# POWER_IO.net
KiCad netlist of a schematic drawn in Altium Designer
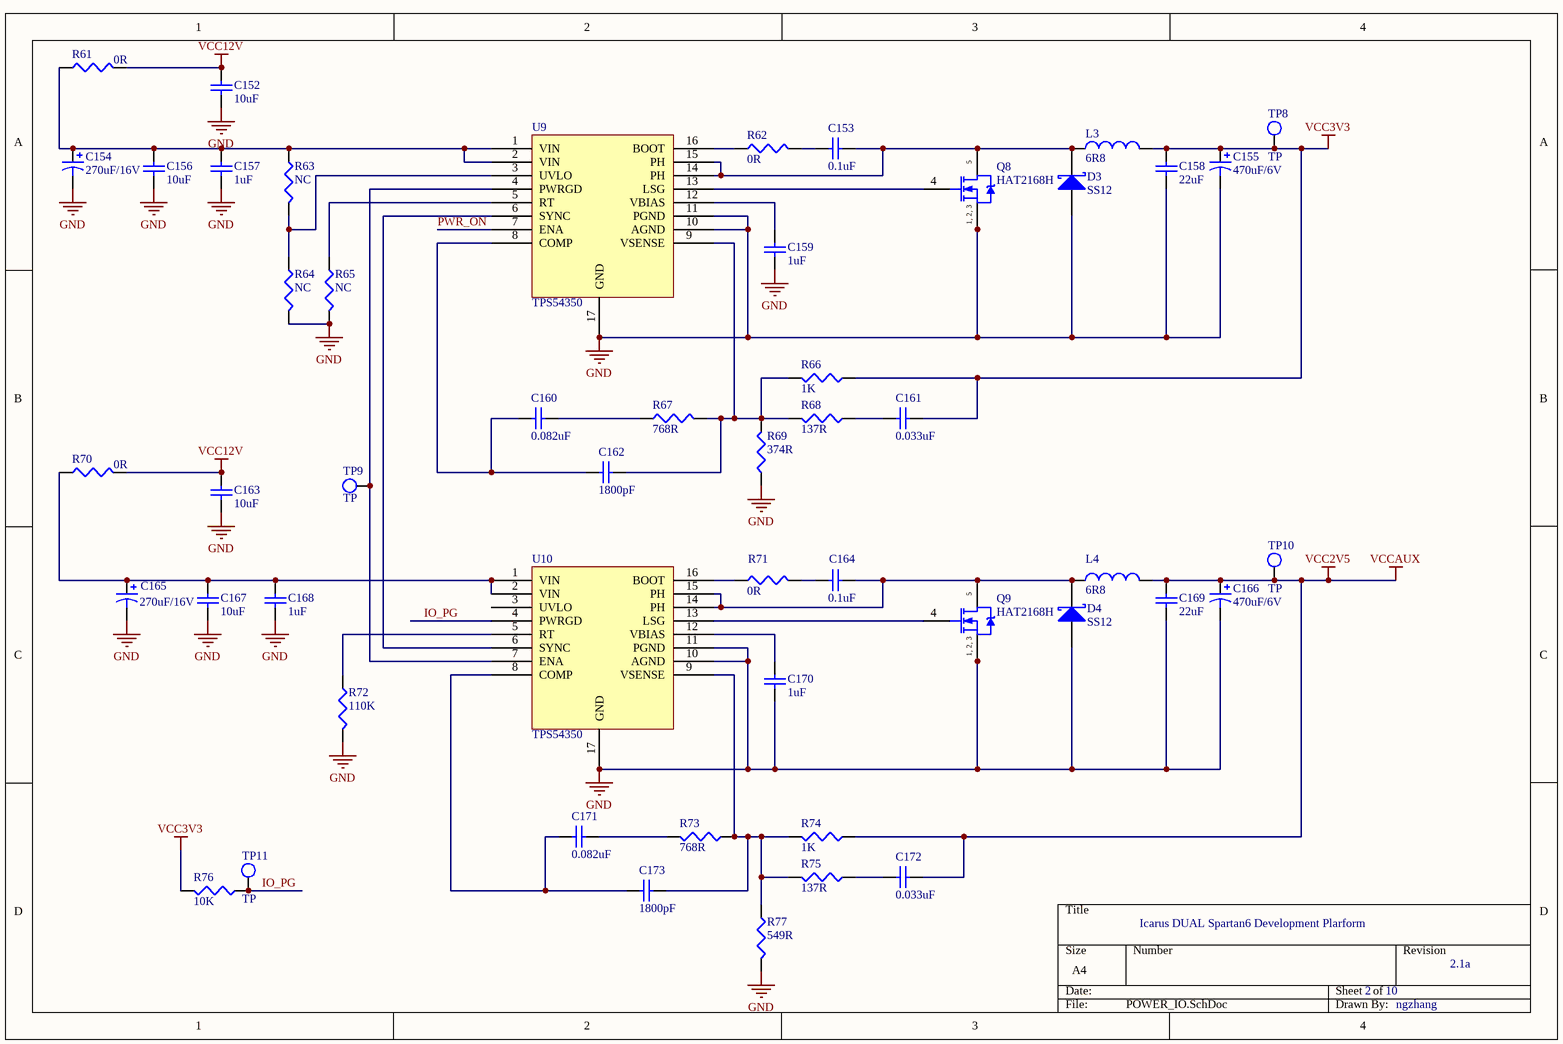
[diagram p0: POWER_IO.SchDoc]

(export (version "E")
  (design (tool "Eeschema 10.0.6"))
  (components
    (comp (ref "C152")
      (value "10uF")
      (footprint "C1206")
      (description "Capacitor (Semiconductor SIM Model)")
      (fields (field (name "PUBLISHER") "Altium Limited"))
      (libsource (lib "Miscellaneous Devices") (part "Cap Semi"))
    )
    (comp (ref "C153")
      (value "0.1uF")
      (footprint "1608[0603]")
      (description "Capacitor (Semiconductor SIM Model)")
      (fields (field (name "PUBLISHER") "Altium Limited"))
      (libsource (lib "Miscellaneous Devices") (part "Cap Semi"))
    )
    (comp (ref "C154")
      (value "270uF/16V")
      (footprint "CAP8X8")
      (description "Polarized Capacitor (Surface Mount)")
      (fields (field (name "PUBLISHER") "Altium Limited"))
      (libsource (lib "Miscellaneous Devices") (part "Cap Pol3"))
    )
    (comp (ref "C155")
      (value "470uF/6V")
      (footprint "CAP8X8")
      (description "Polarized Capacitor (Surface Mount)")
      (fields (field (name "PUBLISHER") "Altium Limited"))
      (libsource (lib "Miscellaneous Devices") (part "Cap Pol3"))
    )
    (comp (ref "C156")
      (value "10uF")
      (footprint "C1206")
      (description "Capacitor (Semiconductor SIM Model)")
      (fields (field (name "PUBLISHER") "Altium Limited"))
      (libsource (lib "Miscellaneous Devices") (part "Cap Semi"))
    )
    (comp (ref "C157")
      (value "1uF")
      (footprint "1608[0603]")
      (description "Capacitor (Semiconductor SIM Model)")
      (fields (field (name "PUBLISHER") "Altium Limited"))
      (libsource (lib "Miscellaneous Devices") (part "Cap Semi"))
    )
    (comp (ref "C158")
      (value "22uF")
      (footprint "C1206")
      (description "Capacitor (Semiconductor SIM Model)")
      (fields (field (name "PUBLISHER") "Altium Limited"))
      (libsource (lib "Miscellaneous Devices") (part "Cap Semi"))
    )
    (comp (ref "C159")
      (value "1uF")
      (footprint "1608[0603]")
      (description "Capacitor (Semiconductor SIM Model)")
      (fields (field (name "PUBLISHER") "Altium Limited"))
      (libsource (lib "Miscellaneous Devices") (part "Cap Semi"))
    )
    (comp (ref "C160")
      (value "0.082uF")
      (footprint "1608[0603]")
      (description "Capacitor (Semiconductor SIM Model)")
      (fields (field (name "PUBLISHER") "Altium Limited"))
      (libsource (lib "Miscellaneous Devices") (part "Cap Semi"))
    )
    (comp (ref "C161")
      (value "0.033uF")
      (footprint "1608[0603]")
      (description "Capacitor (Semiconductor SIM Model)")
      (fields (field (name "PUBLISHER") "Altium Limited"))
      (libsource (lib "Miscellaneous Devices") (part "Cap Semi"))
    )
    (comp (ref "C162")
      (value "1800pF")
      (footprint "1608[0603]")
      (description "Capacitor (Semiconductor SIM Model)")
      (fields (field (name "PUBLISHER") "Altium Limited"))
      (libsource (lib "Miscellaneous Devices") (part "Cap Semi"))
    )
    (comp (ref "C163")
      (value "10uF")
      (footprint "C1206")
      (description "Capacitor (Semiconductor SIM Model)")
      (fields (field (name "PUBLISHER") "Altium Limited"))
      (libsource (lib "Miscellaneous Devices") (part "Cap Semi"))
    )
    (comp (ref "C164")
      (value "0.1uF")
      (footprint "1608[0603]")
      (description "Capacitor (Semiconductor SIM Model)")
      (fields (field (name "PUBLISHER") "Altium Limited"))
      (libsource (lib "Miscellaneous Devices") (part "Cap Semi"))
    )
    (comp (ref "C165")
      (value "270uF/16V")
      (footprint "CAP8X8")
      (description "Polarized Capacitor (Surface Mount)")
      (fields (field (name "PUBLISHER") "Altium Limited"))
      (libsource (lib "Miscellaneous Devices") (part "Cap Pol3"))
    )
    (comp (ref "C166")
      (value "470uF/6V")
      (footprint "CAP8X8")
      (description "Polarized Capacitor (Surface Mount)")
      (fields (field (name "PUBLISHER") "Altium Limited"))
      (libsource (lib "Miscellaneous Devices") (part "Cap Pol3"))
    )
    (comp (ref "C167")
      (value "10uF")
      (footprint "C1206")
      (description "Capacitor (Semiconductor SIM Model)")
      (fields (field (name "PUBLISHER") "Altium Limited"))
      (libsource (lib "Miscellaneous Devices") (part "Cap Semi"))
    )
    (comp (ref "C168")
      (value "1uF")
      (footprint "1608[0603]")
      (description "Capacitor (Semiconductor SIM Model)")
      (fields (field (name "PUBLISHER") "Altium Limited"))
      (libsource (lib "Miscellaneous Devices") (part "Cap Semi"))
    )
    (comp (ref "C169")
      (value "22uF")
      (footprint "C1206")
      (description "Capacitor (Semiconductor SIM Model)")
      (fields (field (name "PUBLISHER") "Altium Limited"))
      (libsource (lib "Miscellaneous Devices") (part "Cap Semi"))
    )
    (comp (ref "C170")
      (value "1uF")
      (footprint "1608[0603]")
      (description "Capacitor (Semiconductor SIM Model)")
      (fields (field (name "PUBLISHER") "Altium Limited"))
      (libsource (lib "Miscellaneous Devices") (part "Cap Semi"))
    )
    (comp (ref "C171")
      (value "0.082uF")
      (footprint "1608[0603]")
      (description "Capacitor (Semiconductor SIM Model)")
      (fields (field (name "PUBLISHER") "Altium Limited"))
      (libsource (lib "Miscellaneous Devices") (part "Cap Semi"))
    )
    (comp (ref "C172")
      (value "0.033uF")
      (footprint "1608[0603]")
      (description "Capacitor (Semiconductor SIM Model)")
      (fields (field (name "PUBLISHER") "Altium Limited"))
      (libsource (lib "Miscellaneous Devices") (part "Cap Semi"))
    )
    (comp (ref "C173")
      (value "1800pF")
      (footprint "1608[0603]")
      (description "Capacitor (Semiconductor SIM Model)")
      (fields (field (name "PUBLISHER") "Altium Limited"))
      (libsource (lib "Miscellaneous Devices") (part "Cap Semi"))
    )
    (comp (ref "D3")
      (value "SS12")
      (footprint "SMA")
      (description "Schottky Rectifier")
      (fields (field (name "PUBLISHER") "Altium Limited"))
      (libsource (lib "IR Rectifier - Schottky") (part "10MQ060N"))
    )
    (comp (ref "D4")
      (value "SS12")
      (footprint "SMA")
      (description "Schottky Rectifier")
      (fields (field (name "PUBLISHER") "Altium Limited"))
      (libsource (lib "IR Rectifier - Schottky") (part "10MQ060N"))
    )
    (comp (ref "L3")
      (value "6R8")
      (footprint "IHLP4040")
      (description "Inductor")
      (fields (field (name "Comment") "IHLP4040DZ11") (field (name "PUBLISHER") "Altium Limited"))
      (libsource (lib "Miscellaneous Devices") (part "Inductor"))
    )
    (comp (ref "L4")
      (value "6R8")
      (footprint "IHLP4040")
      (description "Inductor")
      (fields (field (name "Comment") "IHLP4040DZ11") (field (name "PUBLISHER") "Altium Limited"))
      (libsource (lib "Miscellaneous Devices") (part "Inductor"))
    )
    (comp (ref "Q8") (value "HAT2168H") (footprint "LFPAK") (libsource (lib "S6") (part "HAT216X")))
    (comp (ref "Q9") (value "HAT2168H") (footprint "LFPAK") (libsource (lib "S6") (part "HAT216X")))
    (comp (ref "R61")
      (value "0R")
      (footprint "C1206")
      (description "Resistor")
      (fields (field (name "PUBLISHER") "Altium Limited"))
      (libsource (lib "Miscellaneous Devices") (part "Res3"))
    )
    (comp (ref "R62")
      (value "0R")
      (footprint "J1-0603")
      (description "Resistor")
      (fields (field (name "PUBLISHER") "Altium Limited"))
      (libsource (lib "Miscellaneous Devices") (part "Res3"))
    )
    (comp (ref "R63")
      (value "NC")
      (footprint "J1-0603")
      (description "Resistor")
      (fields (field (name "PUBLISHER") "Altium Limited"))
      (libsource (lib "Miscellaneous Devices") (part "Res3"))
    )
    (comp (ref "R64")
      (value "NC")
      (footprint "J1-0603")
      (description "Resistor")
      (fields (field (name "PUBLISHER") "Altium Limited"))
      (libsource (lib "Miscellaneous Devices") (part "Res3"))
    )
    (comp (ref "R65")
      (value "NC")
      (footprint "J1-0603")
      (description "Resistor")
      (fields (field (name "PUBLISHER") "Altium Limited"))
      (libsource (lib "Miscellaneous Devices") (part "Res3"))
    )
    (comp (ref "R66")
      (value "1K")
      (footprint "J1-0603")
      (description "Resistor")
      (fields (field (name "PUBLISHER") "Altium Limited"))
      (libsource (lib "Miscellaneous Devices") (part "Res3"))
    )
    (comp (ref "R67")
      (value "768R")
      (footprint "J1-0603")
      (description "Resistor")
      (fields (field (name "PUBLISHER") "Altium Limited"))
      (libsource (lib "Miscellaneous Devices") (part "Res3"))
    )
    (comp (ref "R68")
      (value "137R")
      (footprint "J1-0603")
      (description "Resistor")
      (fields (field (name "PUBLISHER") "Altium Limited"))
      (libsource (lib "Miscellaneous Devices") (part "Res3"))
    )
    (comp (ref "R69")
      (value "374R")
      (footprint "J1-0603")
      (description "Resistor")
      (fields (field (name "PUBLISHER") "Altium Limited"))
      (libsource (lib "Miscellaneous Devices") (part "Res3"))
    )
    (comp (ref "R70")
      (value "0R")
      (footprint "C1206")
      (description "Resistor")
      (fields (field (name "PUBLISHER") "Altium Limited"))
      (libsource (lib "Miscellaneous Devices") (part "Res3"))
    )
    (comp (ref "R71")
      (value "0R")
      (footprint "J1-0603")
      (description "Resistor")
      (fields (field (name "PUBLISHER") "Altium Limited"))
      (libsource (lib "Miscellaneous Devices") (part "Res3"))
    )
    (comp (ref "R72")
      (value "110K")
      (footprint "J1-0603")
      (description "Resistor")
      (fields (field (name "PUBLISHER") "Altium Limited"))
      (libsource (lib "Miscellaneous Devices") (part "Res3"))
    )
    (comp (ref "R73")
      (value "768R")
      (footprint "J1-0603")
      (description "Resistor")
      (fields (field (name "PUBLISHER") "Altium Limited"))
      (libsource (lib "Miscellaneous Devices") (part "Res3"))
    )
    (comp (ref "R74")
      (value "1K")
      (footprint "J1-0603")
      (description "Resistor")
      (fields (field (name "PUBLISHER") "Altium Limited"))
      (libsource (lib "Miscellaneous Devices") (part "Res3"))
    )
    (comp (ref "R75")
      (value "137R")
      (footprint "J1-0603")
      (description "Resistor")
      (fields (field (name "PUBLISHER") "Altium Limited"))
      (libsource (lib "Miscellaneous Devices") (part "Res3"))
    )
    (comp (ref "R76")
      (value "10K")
      (footprint "J1-0603")
      (description "Resistor")
      (fields (field (name "PUBLISHER") "Altium Limited"))
      (libsource (lib "Miscellaneous Devices") (part "Res3"))
    )
    (comp (ref "R77")
      (value "549R")
      (footprint "J1-0603")
      (description "Resistor")
      (fields (field (name "PUBLISHER") "Altium Limited"))
      (libsource (lib "Miscellaneous Devices") (part "Res3"))
    )
    (comp (ref "TP8") (value "TP") (footprint "TP") (libsource (lib "S6") (part "TP")))
    (comp (ref "TP9") (value "TP") (footprint "TP") (libsource (lib "S6") (part "TP")))
    (comp (ref "TP10") (value "TP") (footprint "TP") (libsource (lib "S6") (part "TP")))
    (comp (ref "TP11") (value "TP") (footprint "TP") (libsource (lib "S6") (part "TP")))
    (comp (ref "U9") (value "TPS54350") (footprint "TSSOP16_PP") (libsource (lib "S6") (part "TPS54350")))
    (comp (ref "U10") (value "TPS54350") (footprint "TSSOP16_PP") (libsource (lib "S6") (part "TPS54350")))
  )
  (nets
    (net (code "1") (name "/IO_PG") (class "Default")
      (node (ref "R76") (pin "1") (pinfunction "1_1") (pintype "passive"))
      (node (ref "TP11") (pin "1") (pinfunction "TP_1") (pintype "passive"))
      (node (ref "U10") (pin "4") (pinfunction "PWRGD_4") (pintype "passive"))
    )
    (net (code "2") (name "/PWR_ON") (class "Default")
      (node (ref "U9") (pin "7") (pinfunction "ENA_7") (pintype "passive"))
    )
    (net (code "3") (name "GND") (class "Default")
      (node (ref "C152") (pin "1") (pinfunction "1_1") (pintype "passive"))
      (node (ref "C154") (pin "2") (pinfunction "2_2") (pintype "passive"))
      (node (ref "C155") (pin "2") (pinfunction "2_2") (pintype "passive"))
      (node (ref "C156") (pin "1") (pinfunction "1_1") (pintype "passive"))
      (node (ref "C157") (pin "1") (pinfunction "1_1") (pintype "passive"))
      (node (ref "C158") (pin "1") (pinfunction "1_1") (pintype "passive"))
      (node (ref "C159") (pin "1") (pinfunction "1_1") (pintype "passive"))
      (node (ref "C163") (pin "1") (pinfunction "1_1") (pintype "passive"))
      (node (ref "C165") (pin "2") (pinfunction "2_2") (pintype "passive"))
      (node (ref "C166") (pin "2") (pinfunction "2_2") (pintype "passive"))
      (node (ref "C167") (pin "1") (pinfunction "1_1") (pintype "passive"))
      (node (ref "C168") (pin "1") (pinfunction "1_1") (pintype "passive"))
      (node (ref "C169") (pin "1") (pinfunction "1_1") (pintype "passive"))
      (node (ref "C170") (pin "2") (pinfunction "2_2") (pintype "passive"))
      (node (ref "D3") (pin "1") (pinfunction "A_1") (pintype "passive"))
      (node (ref "D4") (pin "1") (pinfunction "A_1") (pintype "passive"))
      (node (ref "Q8") (pin "1") (pinfunction "S_1") (pintype "passive"))
      (node (ref "Q8") (pin "2") (pinfunction "S_2") (pintype "passive"))
      (node (ref "Q8") (pin "3") (pinfunction "S_3") (pintype "passive"))
      (node (ref "Q9") (pin "1") (pinfunction "S_1") (pintype "passive"))
      (node (ref "Q9") (pin "2") (pinfunction "S_2") (pintype "passive"))
      (node (ref "Q9") (pin "3") (pinfunction "S_3") (pintype "passive"))
      (node (ref "R64") (pin "2") (pinfunction "2_2") (pintype "passive"))
      (node (ref "R65") (pin "2") (pinfunction "2_2") (pintype "passive"))
      (node (ref "R69") (pin "1") (pinfunction "1_1") (pintype "passive"))
      (node (ref "R72") (pin "2") (pinfunction "2_2") (pintype "passive"))
      (node (ref "R77") (pin "2") (pinfunction "2_2") (pintype "passive"))
      (node (ref "U10") (pin "10") (pinfunction "AGND_10") (pintype "passive"))
      (node (ref "U10") (pin "11") (pinfunction "PGND_11") (pintype "passive"))
      (node (ref "U10") (pin "17") (pinfunction "GND_17") (pintype "power_in"))
      (node (ref "U9") (pin "10") (pinfunction "AGND_10") (pintype "passive"))
      (node (ref "U9") (pin "11") (pinfunction "PGND_11") (pintype "passive"))
      (node (ref "U9") (pin "17") (pinfunction "GND_17") (pintype "power_in"))
    )
    (net (code "4") (name "Net-(C153-Pad1)") (class "Default")
      (node (ref "C153") (pin "1") (pinfunction "1_1") (pintype "passive"))
      (node (ref "R62") (pin "2") (pinfunction "2_2") (pintype "passive"))
    )
    (net (code "5") (name "Net-(C154-Pad1)") (class "Default")
      (node (ref "C154") (pin "1") (pinfunction "1_1") (pintype "passive"))
      (node (ref "C156") (pin "2") (pinfunction "2_2") (pintype "passive"))
      (node (ref "C157") (pin "2") (pinfunction "2_2") (pintype "passive"))
      (node (ref "R61") (pin "1") (pinfunction "1_1") (pintype "passive"))
      (node (ref "R63") (pin "1") (pinfunction "1_1") (pintype "passive"))
      (node (ref "U9") (pin "1") (pinfunction "VIN_1") (pintype "power_in"))
      (node (ref "U9") (pin "2") (pinfunction "VIN_2") (pintype "power_in"))
    )
    (net (code "6") (name "Net-(C160-Pad2)") (class "Default")
      (node (ref "C160") (pin "2") (pinfunction "2_2") (pintype "passive"))
      (node (ref "R67") (pin "1") (pinfunction "1_1") (pintype "passive"))
    )
    (net (code "7") (name "Net-(C161-Pad1)") (class "Default")
      (node (ref "C161") (pin "1") (pinfunction "1_1") (pintype "passive"))
      (node (ref "R68") (pin "1") (pinfunction "1_1") (pintype "passive"))
    )
    (net (code "8") (name "Net-(C164-Pad2)") (class "Default")
      (node (ref "C164") (pin "2") (pinfunction "2_2") (pintype "passive"))
      (node (ref "R71") (pin "2") (pinfunction "2_2") (pintype "passive"))
    )
    (net (code "9") (name "Net-(C165-Pad1)") (class "Default")
      (node (ref "C165") (pin "1") (pinfunction "1_1") (pintype "passive"))
      (node (ref "C167") (pin "2") (pinfunction "2_2") (pintype "passive"))
      (node (ref "C168") (pin "2") (pinfunction "2_2") (pintype "passive"))
      (node (ref "R70") (pin "1") (pinfunction "1_1") (pintype "passive"))
      (node (ref "U10") (pin "1") (pinfunction "VIN_1") (pintype "power_in"))
      (node (ref "U10") (pin "2") (pinfunction "VIN_2") (pintype "power_in"))
    )
    (net (code "10") (name "Net-(C171-Pad2)") (class "Default")
      (node (ref "C171") (pin "2") (pinfunction "2_2") (pintype "passive"))
      (node (ref "R73") (pin "2") (pinfunction "2_2") (pintype "passive"))
    )
    (net (code "11") (name "Net-(C172-Pad1)") (class "Default")
      (node (ref "C172") (pin "1") (pinfunction "1_1") (pintype "passive"))
      (node (ref "R75") (pin "1") (pinfunction "1_1") (pintype "passive"))
    )
    (net (code "12") (name "Net-(D3-K)") (class "Default")
      (node (ref "C153") (pin "2") (pinfunction "2_2") (pintype "passive"))
      (node (ref "D3") (pin "2") (pinfunction "K_2") (pintype "passive"))
      (node (ref "L3") (pin "1") (pinfunction "1_1") (pintype "passive"))
      (node (ref "Q8") (pin "5") (pinfunction "D_5") (pintype "passive"))
      (node (ref "U9") (pin "14") (pinfunction "PH_14") (pintype "passive"))
      (node (ref "U9") (pin "15") (pinfunction "PH_15") (pintype "passive"))
    )
    (net (code "13") (name "Net-(D4-K)") (class "Default")
      (node (ref "C164") (pin "1") (pinfunction "1_1") (pintype "passive"))
      (node (ref "D4") (pin "2") (pinfunction "K_2") (pintype "passive"))
      (node (ref "L4") (pin "1") (pinfunction "1_1") (pintype "passive"))
      (node (ref "Q9") (pin "5") (pinfunction "D_5") (pintype "passive"))
      (node (ref "U10") (pin "14") (pinfunction "PH_14") (pintype "passive"))
      (node (ref "U10") (pin "15") (pinfunction "PH_15") (pintype "passive"))
    )
    (net (code "14") (name "Net-(Q8-G)") (class "Default")
      (node (ref "Q8") (pin "4") (pinfunction "G_4") (pintype "passive"))
      (node (ref "U9") (pin "13") (pinfunction "LSG_13") (pintype "passive"))
    )
    (net (code "15") (name "Net-(Q9-G)") (class "Default")
      (node (ref "Q9") (pin "4") (pinfunction "G_4") (pintype "passive"))
      (node (ref "U10") (pin "13") (pinfunction "LSG_13") (pintype "passive"))
    )
    (net (code "16") (name "Net-(TP9-TP)") (class "Default")
      (node (ref "TP9") (pin "1") (pinfunction "TP_1") (pintype "passive"))
      (node (ref "U10") (pin "7") (pinfunction "ENA_7") (pintype "passive"))
      (node (ref "U9") (pin "4") (pinfunction "PWRGD_4") (pintype "passive"))
    )
    (net (code "17") (name "Net-(U9-BOOT)") (class "Default")
      (node (ref "R62") (pin "1") (pinfunction "1_1") (pintype "passive"))
      (node (ref "U9") (pin "16") (pinfunction "BOOT_16") (pintype "passive"))
    )
    (net (code "18") (name "Net-(U9-COMP)") (class "Default")
      (node (ref "C160") (pin "1") (pinfunction "1_1") (pintype "passive"))
      (node (ref "C162") (pin "1") (pinfunction "1_1") (pintype "passive"))
      (node (ref "U9") (pin "8") (pinfunction "COMP_8") (pintype "passive"))
    )
    (net (code "19") (name "Net-(U9-RT)") (class "Default")
      (node (ref "R65") (pin "1") (pinfunction "1_1") (pintype "passive"))
      (node (ref "U9") (pin "5") (pinfunction "RT_5") (pintype "passive"))
    )
    (net (code "20") (name "Net-(U9-UVLO)") (class "Default")
      (node (ref "R63") (pin "2") (pinfunction "2_2") (pintype "passive"))
      (node (ref "R64") (pin "1") (pinfunction "1_1") (pintype "passive"))
      (node (ref "U9") (pin "3") (pinfunction "UVLO_3") (pintype "passive"))
    )
    (net (code "21") (name "Net-(U9-VBIAS)") (class "Default")
      (node (ref "C159") (pin "2") (pinfunction "2_2") (pintype "passive"))
      (node (ref "U9") (pin "12") (pinfunction "VBIAS_12") (pintype "passive"))
    )
    (net (code "22") (name "Net-(U9-VSENSE)") (class "Default")
      (node (ref "C162") (pin "2") (pinfunction "2_2") (pintype "passive"))
      (node (ref "R66") (pin "2") (pinfunction "2_2") (pintype "passive"))
      (node (ref "R67") (pin "2") (pinfunction "2_2") (pintype "passive"))
      (node (ref "R68") (pin "2") (pinfunction "2_2") (pintype "passive"))
      (node (ref "R69") (pin "2") (pinfunction "2_2") (pintype "passive"))
      (node (ref "U9") (pin "9") (pinfunction "VSENSE_9") (pintype "passive"))
    )
    (net (code "23") (name "Net-(U10-BOOT)") (class "Default")
      (node (ref "R71") (pin "1") (pinfunction "1_1") (pintype "passive"))
      (node (ref "U10") (pin "16") (pinfunction "BOOT_16") (pintype "passive"))
    )
    (net (code "24") (name "Net-(U10-COMP)") (class "Default")
      (node (ref "C171") (pin "1") (pinfunction "1_1") (pintype "passive"))
      (node (ref "C173") (pin "1") (pinfunction "1_1") (pintype "passive"))
      (node (ref "U10") (pin "8") (pinfunction "COMP_8") (pintype "passive"))
    )
    (net (code "25") (name "Net-(U10-RT)") (class "Default")
      (node (ref "R72") (pin "1") (pinfunction "1_1") (pintype "passive"))
      (node (ref "U10") (pin "5") (pinfunction "RT_5") (pintype "passive"))
    )
    (net (code "26") (name "Net-(U10-SYNC)") (class "Default")
      (node (ref "U10") (pin "6") (pinfunction "SYNC_6") (pintype "passive"))
      (node (ref "U9") (pin "6") (pinfunction "SYNC_6") (pintype "passive"))
    )
    (net (code "27") (name "Net-(U10-VBIAS)") (class "Default")
      (node (ref "C170") (pin "1") (pinfunction "1_1") (pintype "passive"))
      (node (ref "U10") (pin "12") (pinfunction "VBIAS_12") (pintype "passive"))
    )
    (net (code "28") (name "Net-(U10-VSENSE)") (class "Default")
      (node (ref "C173") (pin "2") (pinfunction "2_2") (pintype "passive"))
      (node (ref "R73") (pin "1") (pinfunction "1_1") (pintype "passive"))
      (node (ref "R74") (pin "2") (pinfunction "2_2") (pintype "passive"))
      (node (ref "R75") (pin "2") (pinfunction "2_2") (pintype "passive"))
      (node (ref "R77") (pin "1") (pinfunction "1_1") (pintype "passive"))
      (node (ref "U10") (pin "9") (pinfunction "VSENSE_9") (pintype "passive"))
    )
    (net (code "29") (name "VCC2V5") (class "Default")
      (node (ref "C166") (pin "1") (pinfunction "1_1") (pintype "passive"))
      (node (ref "C169") (pin "2") (pinfunction "2_2") (pintype "passive"))
      (node (ref "C172") (pin "2") (pinfunction "2_2") (pintype "passive"))
      (node (ref "L4") (pin "2") (pinfunction "2_2") (pintype "passive"))
      (node (ref "R74") (pin "1") (pinfunction "1_1") (pintype "passive"))
      (node (ref "TP10") (pin "1") (pinfunction "TP_1") (pintype "passive"))
    )
    (net (code "30") (name "VCC3V3") (class "Default")
      (node (ref "C155") (pin "1") (pinfunction "1_1") (pintype "passive"))
      (node (ref "C158") (pin "2") (pinfunction "2_2") (pintype "passive"))
      (node (ref "C161") (pin "2") (pinfunction "2_2") (pintype "passive"))
      (node (ref "L3") (pin "2") (pinfunction "2_2") (pintype "passive"))
      (node (ref "R66") (pin "1") (pinfunction "1_1") (pintype "passive"))
      (node (ref "R76") (pin "2") (pinfunction "2_2") (pintype "passive"))
      (node (ref "TP8") (pin "1") (pinfunction "TP_1") (pintype "passive"))
    )
    (net (code "31") (name "VCC12V") (class "Default")
      (node (ref "C152") (pin "2") (pinfunction "2_2") (pintype "passive"))
      (node (ref "C163") (pin "2") (pinfunction "2_2") (pintype "passive"))
      (node (ref "R61") (pin "2") (pinfunction "2_2") (pintype "passive"))
      (node (ref "R70") (pin "2") (pinfunction "2_2") (pintype "passive"))
    )
    (net (code "32") (name "unconnected-(U10-UVLO-Pad3)") (class "Default")
      (node (ref "U10") (pin "3") (pinfunction "UVLO_3") (pintype "passive"))
    )
  )
)
